# FPGA_Power_Ports.net
KiCad netlist of a schematic drawn in Altium Designer
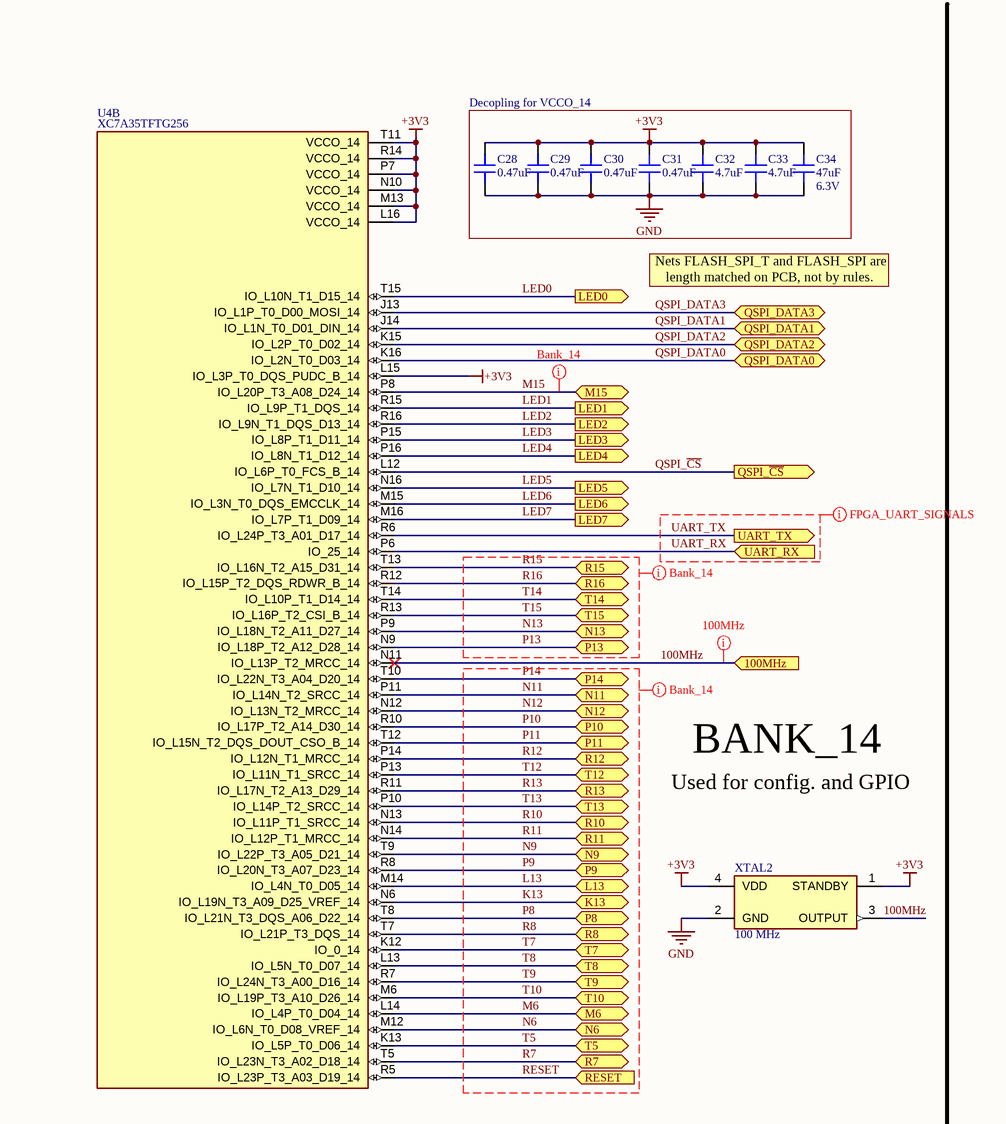
[diagram p0: FPGA_Power&Ports.SchDoc, top left]
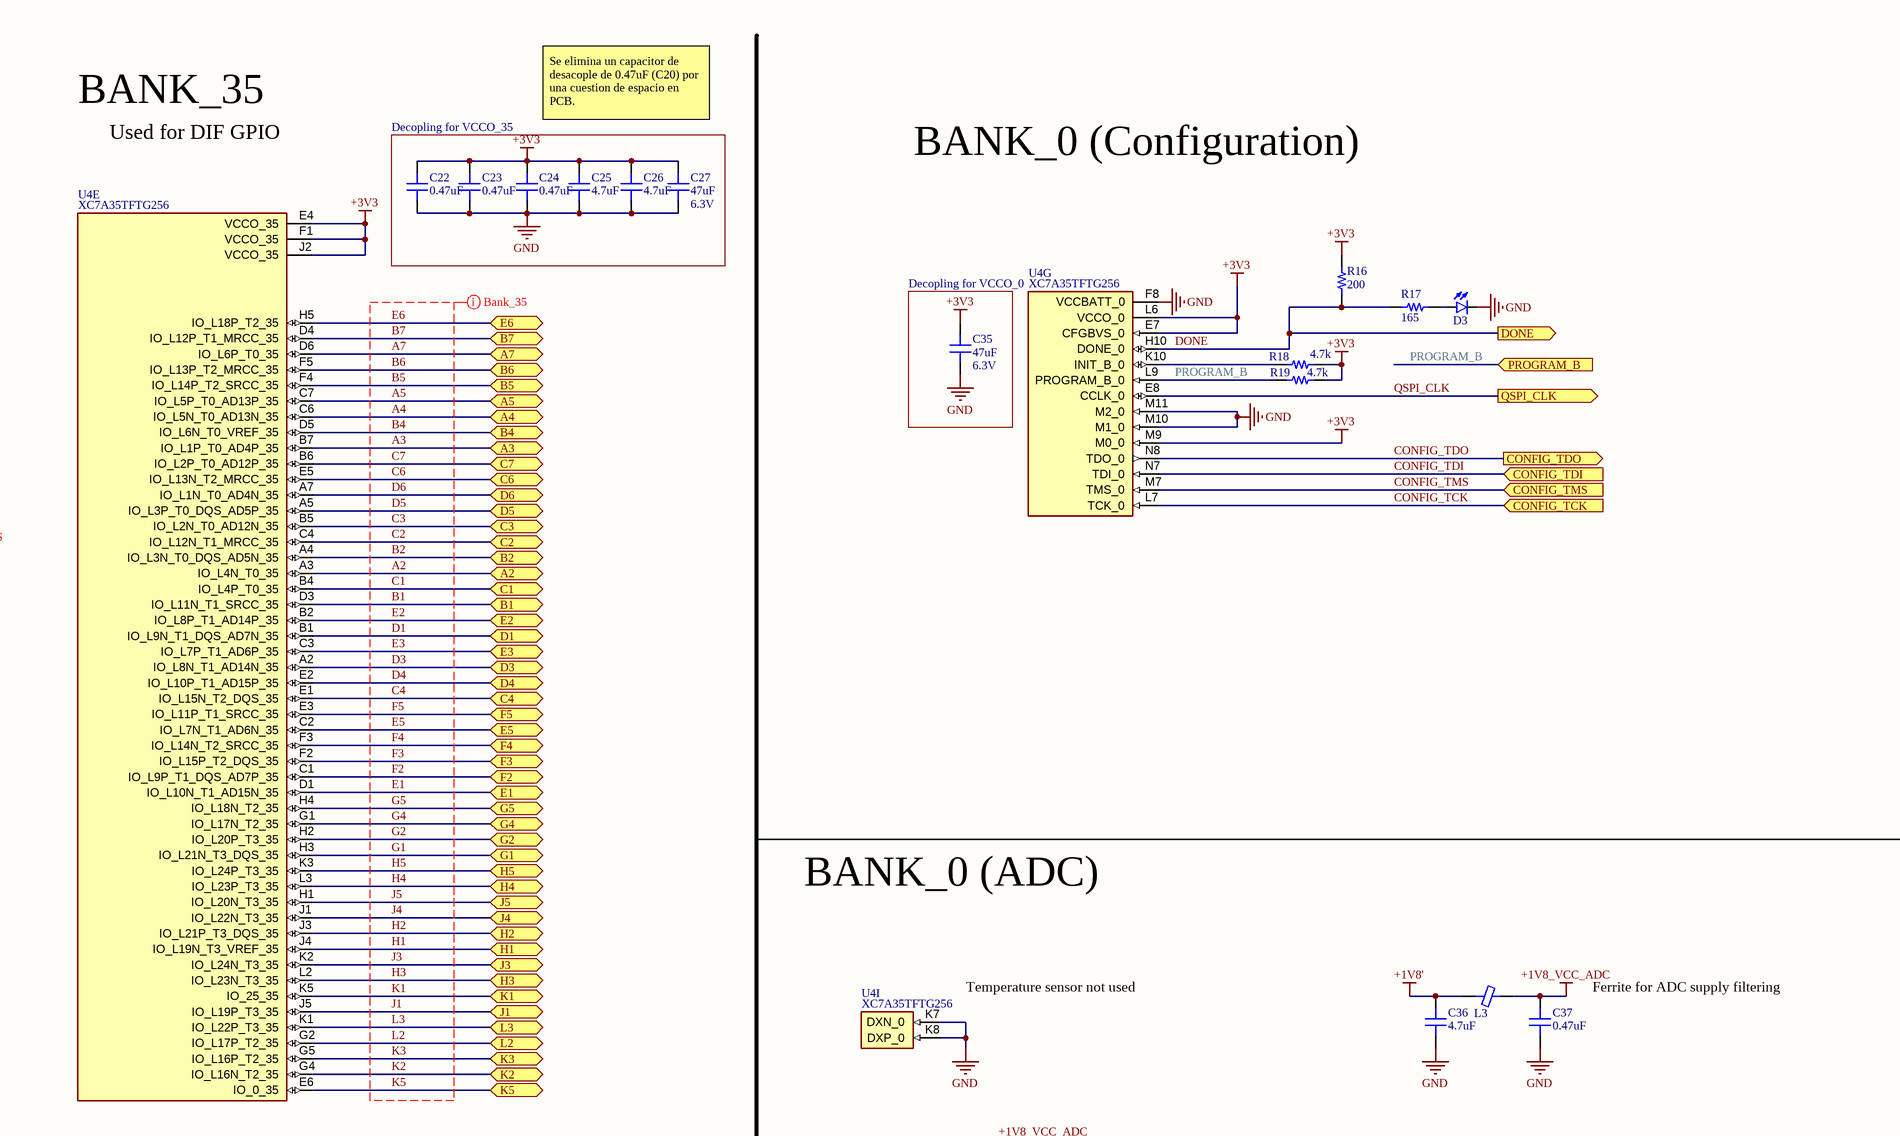
[diagram p1: FPGA_Power&Ports.SchDoc, top right]
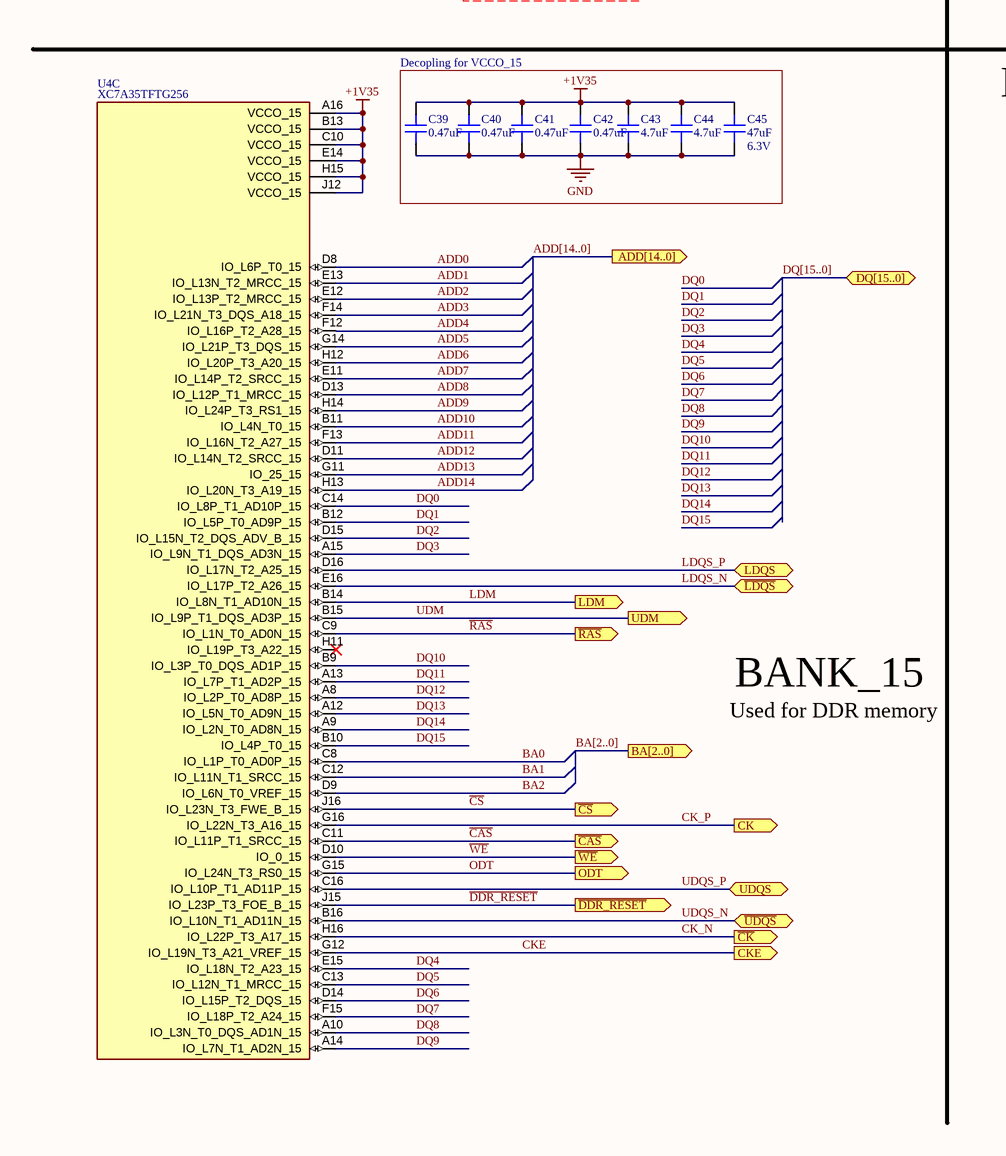
[diagram p2: FPGA_Power&Ports.SchDoc, bottom left]
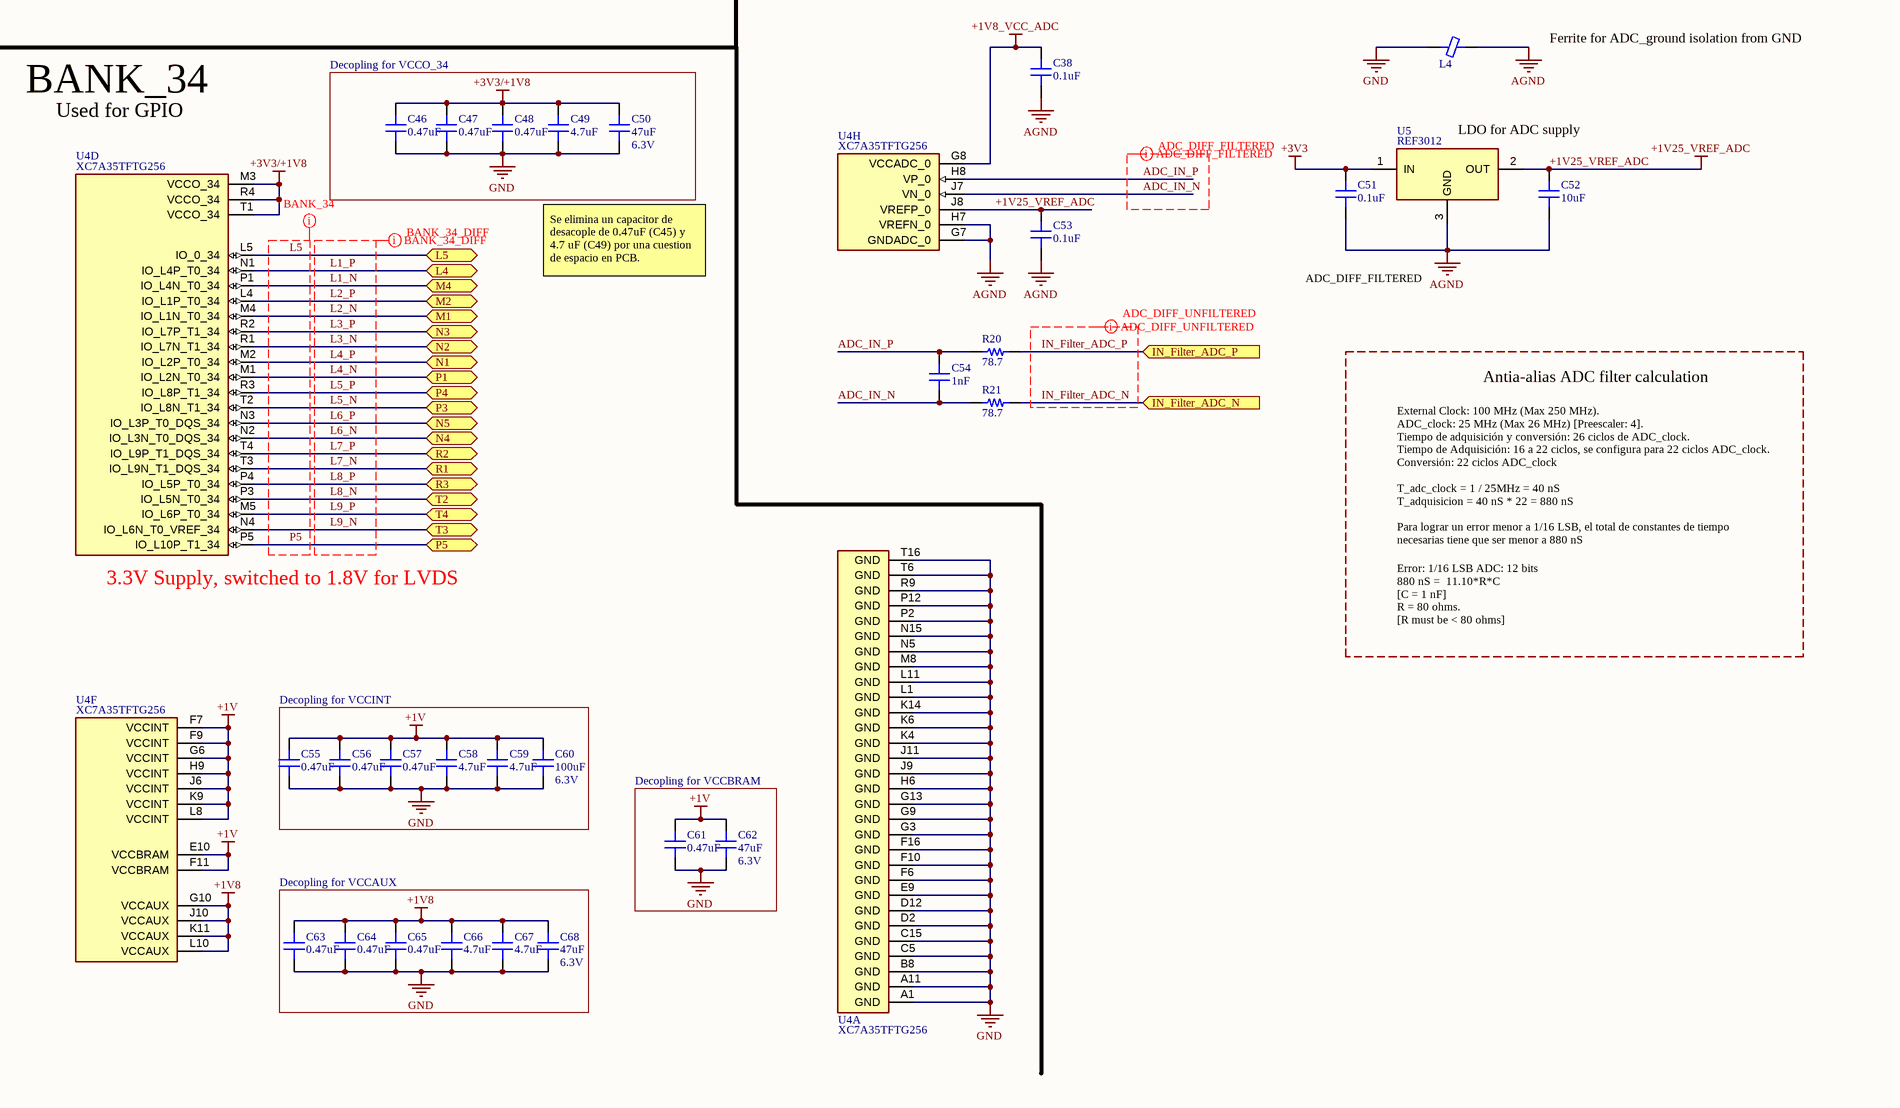
[diagram p3: FPGA_Power&Ports.SchDoc, bottom right]

(export (version "E")
  (design (tool "Eeschema 10.0.6"))
  (components
    (comp (ref "C22")
      (value "0.47uF")
      (footprint "CAP0402")
      (description "CAP CER 0.47uF 10V X7R 0402 10%")
      (fields (field (name "PARTNUMBER") "C0603C474K4RAC") (field (name "TOLERANCE") "10%"))
      (libsource (lib "Pasivos") (part "C0402C474K8RAC"))
    )
    (comp (ref "C23")
      (value "0.47uF")
      (footprint "CAP0402")
      (description "CAP CER 0.47uF 10V X7R 0402 10%")
      (fields (field (name "PARTNUMBER") "C0603C474K4RAC") (field (name "TOLERANCE") "10%"))
      (libsource (lib "Pasivos") (part "C0402C474K8RAC"))
    )
    (comp (ref "C24")
      (value "0.47uF")
      (footprint "CAP0402")
      (description "CAP CER 0.47uF 10V X7R 0402 10%")
      (fields (field (name "PARTNUMBER") "C0603C474K4RAC") (field (name "TOLERANCE") "10%"))
      (libsource (lib "Pasivos") (part "C0402C474K8RAC"))
    )
    (comp (ref "C25")
      (value "4.7uF")
      (footprint "CAP0402")
      (description "CAP CER 4.7uF 6.3V X5R 0402 10%")
      (fields (field (name "PARTNUMBER") "C0402C475M9PAC") (field (name "TOLERANCE") "10%"))
      (libsource (lib "Pasivos") (part "C0402C475M9PAC"))
    )
    (comp (ref "C26")
      (value "4.7uF")
      (footprint "CAP0402")
      (description "CAP CER 4.7uF 6.3V X5R 0402 10%")
      (fields (field (name "PARTNUMBER") "C0402C475M9PAC") (field (name "TOLERANCE") "10%"))
      (libsource (lib "Pasivos") (part "C0402C475M9PAC"))
    )
    (comp (ref "C27")
      (value "47uF")
      (footprint "CAP0805")
      (description "CAP CER 47uF 6.3V X5R 0805 20%")
      (fields
        (field (name "VOLTAGE") "6.3V")
        (field (name "MANUFACTURER") "Samsung")
        (field (name "TOLERANCE") "20%")
      )
      (libsource (lib "Pasivos") (part "CL21A476MQYNNNE"))
    )
    (comp (ref "C28")
      (value "0.47uF")
      (footprint "CAP0402")
      (description "CAP CER 0.47uF 10V X7R 0402 10%")
      (fields (field (name "PARTNUMBER") "C0603C474K4RAC") (field (name "TOLERANCE") "10%"))
      (libsource (lib "Pasivos") (part "C0402C474K8RAC"))
    )
    (comp (ref "C29")
      (value "0.47uF")
      (footprint "CAP0402")
      (description "CAP CER 0.47uF 10V X7R 0402 10%")
      (fields (field (name "PARTNUMBER") "C0603C474K4RAC") (field (name "TOLERANCE") "10%"))
      (libsource (lib "Pasivos") (part "C0402C474K8RAC"))
    )
    (comp (ref "C30")
      (value "0.47uF")
      (footprint "CAP0402")
      (description "CAP CER 0.47uF 10V X7R 0402 10%")
      (fields (field (name "PARTNUMBER") "C0603C474K4RAC") (field (name "TOLERANCE") "10%"))
      (libsource (lib "Pasivos") (part "C0402C474K8RAC"))
    )
    (comp (ref "C31")
      (value "0.47uF")
      (footprint "CAP0402")
      (description "CAP CER 0.47uF 10V X7R 0402 10%")
      (fields (field (name "PARTNUMBER") "C0603C474K4RAC") (field (name "TOLERANCE") "10%"))
      (libsource (lib "Pasivos") (part "C0402C474K8RAC"))
    )
    (comp (ref "C32")
      (value "4.7uF")
      (footprint "CAP0402")
      (description "CAP CER 4.7uF 6.3V X5R 0402 10%")
      (fields (field (name "PARTNUMBER") "C0402C475M9PAC") (field (name "TOLERANCE") "10%"))
      (libsource (lib "Pasivos") (part "C0402C475M9PAC"))
    )
    (comp (ref "C33")
      (value "4.7uF")
      (footprint "CAP0402")
      (description "CAP CER 4.7uF 6.3V X5R 0402 10%")
      (fields (field (name "PARTNUMBER") "C0402C475M9PAC") (field (name "TOLERANCE") "10%"))
      (libsource (lib "Pasivos") (part "C0402C475M9PAC"))
    )
    (comp (ref "C34")
      (value "47uF")
      (footprint "CAP0805")
      (description "CAP CER 47uF 6.3V X5R 0805 20%")
      (fields
        (field (name "VOLTAGE") "6.3V")
        (field (name "MANUFACTURER") "Samsung")
        (field (name "TOLERANCE") "20%")
      )
      (libsource (lib "Pasivos") (part "CL21A476MQYNNNE"))
    )
    (comp (ref "C35")
      (value "47uF")
      (footprint "CAP0805")
      (description "CAP CER 47uF 6.3V X5R 0805 20%")
      (fields
        (field (name "MANUFACTURER") "Samsung")
        (field (name "VOLTAGE") "6.3V")
        (field (name "TOLERANCE") "20%")
      )
      (libsource (lib "Pasivos") (part "CL21A476MQYNNNE"))
    )
    (comp (ref "C36")
      (value "4.7uF")
      (footprint "CAP0402")
      (description "CAP CER 4.7uF 6.3V X5R 0402 10%")
      (fields (field (name "PARTNUMBER") "C0402C475M9PAC") (field (name "TOLERANCE") "10%"))
      (libsource (lib "Pasivos") (part "C0402C475M9PAC"))
    )
    (comp (ref "C37")
      (value "0.47uF")
      (footprint "CAP0402")
      (description "CAP CER 0.47uF 10V X7R 0402 10%")
      (fields (field (name "PARTNUMBER") "C0603C474K4RAC") (field (name "TOLERANCE") "10%"))
      (libsource (lib "Pasivos") (part "C0402C474K8RAC"))
    )
    (comp (ref "C38")
      (value "0.1uF")
      (footprint "CAP0402")
      (description "CAP CER 0.1uF 16V X7R 0402 10%")
      (fields (field (name "TOLERANCE") "10%") (field (name "VOLTAGE") "16V"))
      (libsource (lib "Pasivos") (part "C0402C104K4RAC"))
    )
    (comp (ref "C39")
      (value "0.47uF")
      (footprint "CAP0402")
      (description "CAP CER 0.47uF 10V X7R 0402 10%")
      (fields (field (name "PARTNUMBER") "C0603C474K4RAC") (field (name "TOLERANCE") "10%"))
      (libsource (lib "Pasivos") (part "C0402C474K8RAC"))
    )
    (comp (ref "C40")
      (value "0.47uF")
      (footprint "CAP0402")
      (description "CAP CER 0.47uF 10V X7R 0402 10%")
      (fields (field (name "PARTNUMBER") "C0603C474K4RAC") (field (name "TOLERANCE") "10%"))
      (libsource (lib "Pasivos") (part "C0402C474K8RAC"))
    )
    (comp (ref "C41")
      (value "0.47uF")
      (footprint "CAP0402")
      (description "CAP CER 0.47uF 10V X7R 0402 10%")
      (fields (field (name "PARTNUMBER") "C0603C474K4RAC") (field (name "TOLERANCE") "10%"))
      (libsource (lib "Pasivos") (part "C0402C474K8RAC"))
    )
    (comp (ref "C42")
      (value "0.47uF")
      (footprint "CAP0402")
      (description "CAP CER 0.47uF 10V X7R 0402 10%")
      (fields (field (name "PARTNUMBER") "C0603C474K4RAC") (field (name "TOLERANCE") "10%"))
      (libsource (lib "Pasivos") (part "C0402C474K8RAC"))
    )
    (comp (ref "C43")
      (value "4.7uF")
      (footprint "CAP0402")
      (description "CAP CER 4.7uF 6.3V X5R 0402 10%")
      (fields (field (name "PARTNUMBER") "C0402C475M9PAC") (field (name "TOLERANCE") "10%"))
      (libsource (lib "Pasivos") (part "C0402C475M9PAC"))
    )
    (comp (ref "C44")
      (value "4.7uF")
      (footprint "CAP0402")
      (description "CAP CER 4.7uF 6.3V X5R 0402 10%")
      (fields (field (name "PARTNUMBER") "C0402C475M9PAC") (field (name "TOLERANCE") "10%"))
      (libsource (lib "Pasivos") (part "C0402C475M9PAC"))
    )
    (comp (ref "C45")
      (value "47uF")
      (footprint "CAP0805")
      (description "CAP CER 47uF 6.3V X5R 0805 20%")
      (fields
        (field (name "VOLTAGE") "6.3V")
        (field (name "MANUFACTURER") "Samsung")
        (field (name "TOLERANCE") "20%")
      )
      (libsource (lib "Pasivos") (part "CL21A476MQYNNNE"))
    )
    (comp (ref "C46")
      (value "0.47uF")
      (footprint "CAP0402")
      (description "CAP CER 0.47uF 10V X7R 0402 10%")
      (fields (field (name "PARTNUMBER") "C0603C474K4RAC") (field (name "TOLERANCE") "10%"))
      (libsource (lib "Pasivos") (part "C0402C474K8RAC"))
    )
    (comp (ref "C47")
      (value "0.47uF")
      (footprint "CAP0402")
      (description "CAP CER 0.47uF 10V X7R 0402 10%")
      (fields (field (name "PARTNUMBER") "C0603C474K4RAC") (field (name "TOLERANCE") "10%"))
      (libsource (lib "Pasivos") (part "C0402C474K8RAC"))
    )
    (comp (ref "C48")
      (value "0.47uF")
      (footprint "CAP0402")
      (description "CAP CER 0.47uF 10V X7R 0402 10%")
      (fields (field (name "PARTNUMBER") "C0603C474K4RAC") (field (name "TOLERANCE") "10%"))
      (libsource (lib "Pasivos") (part "C0402C474K8RAC"))
    )
    (comp (ref "C49")
      (value "4.7uF")
      (footprint "CAP0402")
      (description "CAP CER 4.7uF 6.3V X5R 0402 10%")
      (fields (field (name "PARTNUMBER") "C0402C475M9PAC") (field (name "TOLERANCE") "10%"))
      (libsource (lib "Pasivos") (part "C0402C475M9PAC"))
    )
    (comp (ref "C50")
      (value "47uF")
      (footprint "CAP0805")
      (description "CAP CER 47uF 6.3V X5R 0805 20%")
      (fields
        (field (name "VOLTAGE") "6.3V")
        (field (name "MANUFACTURER") "Samsung")
        (field (name "TOLERANCE") "20%")
      )
      (libsource (lib "Pasivos") (part "CL21A476MQYNNNE"))
    )
    (comp (ref "C51")
      (value "0.1uF")
      (footprint "CAP0402")
      (description "CAP CER 0.1uF 16V X7R 0402 10%")
      (fields (field (name "TOLERANCE") "10%") (field (name "VOLTAGE") "16V"))
      (libsource (lib "Pasivos") (part "C0402C104K4RAC"))
    )
    (comp (ref "C52")
      (value "10uF")
      (footprint "CAP0402")
      (description "CAP CER 10uF 6.3V X5R 0402 10%")
      (fields (field (name "TOLERANCE") "10%") (field (name "MANUFACTURER") "Kemet"))
      (libsource (lib "Pasivos") (part "C0402C106M9PAC"))
    )
    (comp (ref "C53")
      (value "0.1uF")
      (footprint "CAP0402")
      (description "CAP CER 0.1uF 16V X7R 0402 10%")
      (fields (field (name "TOLERANCE") "10%") (field (name "VOLTAGE") "16V"))
      (libsource (lib "Pasivos") (part "C0402C104K4RAC"))
    )
    (comp (ref "C54")
      (value "1nF")
      (footprint "CAP0402")
      (description "CAP CER 1nF 16V X7R 0402 10%")
      (fields (field (name "TOLERANCE") "10%") (field (name "PARTNUMBER") "C0402C102K4RAC"))
      (libsource (lib "Pasivos") (part "C0402C102K4RAC"))
    )
    (comp (ref "C55")
      (value "0.47uF")
      (footprint "CAP0402")
      (description "CAP CER 0.47uF 10V X7R 0402 10%")
      (fields (field (name "PARTNUMBER") "C0603C474K4RAC") (field (name "TOLERANCE") "10%"))
      (libsource (lib "Pasivos") (part "C0402C474K8RAC"))
    )
    (comp (ref "C56")
      (value "0.47uF")
      (footprint "CAP0402")
      (description "CAP CER 0.47uF 10V X7R 0402 10%")
      (fields (field (name "PARTNUMBER") "C0603C474K4RAC") (field (name "TOLERANCE") "10%"))
      (libsource (lib "Pasivos") (part "C0402C474K8RAC"))
    )
    (comp (ref "C57")
      (value "0.47uF")
      (footprint "CAP0402")
      (description "CAP CER 0.47uF 10V X7R 0402 10%")
      (fields (field (name "PARTNUMBER") "C0603C474K4RAC") (field (name "TOLERANCE") "10%"))
      (libsource (lib "Pasivos") (part "C0402C474K8RAC"))
    )
    (comp (ref "C58")
      (value "4.7uF")
      (footprint "CAP0402")
      (description "CAP CER 4.7uF 6.3V X5R 0402 10%")
      (fields (field (name "PARTNUMBER") "C0402C475M9PAC") (field (name "TOLERANCE") "10%"))
      (libsource (lib "Pasivos") (part "C0402C475M9PAC"))
    )
    (comp (ref "C59")
      (value "4.7uF")
      (footprint "CAP0402")
      (description "CAP CER 4.7uF 6.3V X5R 0402 10%")
      (fields (field (name "PARTNUMBER") "C0402C475M9PAC") (field (name "TOLERANCE") "10%"))
      (libsource (lib "Pasivos") (part "C0402C475M9PAC"))
    )
    (comp (ref "C60")
      (value "100uF")
      (footprint "CAP1206")
      (description "CAP CER 100uF 6.3V X5R 1206 20%")
      (fields
        (field (name "PARTNUMBER") "C1206C107M9PAC")
        (field (name "TOLERANCE") "20%")
        (field (name "VOLTAGE") "6.3V")
      )
      (libsource (lib "Pasivos") (part "C1206C107M9PAC"))
    )
    (comp (ref "C61")
      (value "0.47uF")
      (footprint "CAP0402")
      (description "CAP CER 0.47uF 10V X7R 0402 10%")
      (fields (field (name "PARTNUMBER") "C0603C474K4RAC") (field (name "TOLERANCE") "10%"))
      (libsource (lib "Pasivos") (part "C0402C474K8RAC"))
    )
    (comp (ref "C62")
      (value "47uF")
      (footprint "CAP0805")
      (description "CAP CER 47uF 6.3V X5R 0805 20%")
      (fields
        (field (name "VOLTAGE") "6.3V")
        (field (name "MANUFACTURER") "Samsung")
        (field (name "TOLERANCE") "20%")
      )
      (libsource (lib "Pasivos") (part "CL21A476MQYNNNE"))
    )
    (comp (ref "C63")
      (value "0.47uF")
      (footprint "CAP0402")
      (description "CAP CER 0.47uF 10V X7R 0402 10%")
      (fields (field (name "PARTNUMBER") "C0603C474K4RAC") (field (name "TOLERANCE") "10%"))
      (libsource (lib "Pasivos") (part "C0402C474K8RAC"))
    )
    (comp (ref "C64")
      (value "0.47uF")
      (footprint "CAP0402")
      (description "CAP CER 0.47uF 10V X7R 0402 10%")
      (fields (field (name "PARTNUMBER") "C0603C474K4RAC") (field (name "TOLERANCE") "10%"))
      (libsource (lib "Pasivos") (part "C0402C474K8RAC"))
    )
    (comp (ref "C65")
      (value "0.47uF")
      (footprint "CAP0402")
      (description "CAP CER 0.47uF 10V X7R 0402 10%")
      (fields (field (name "PARTNUMBER") "C0603C474K4RAC") (field (name "TOLERANCE") "10%"))
      (libsource (lib "Pasivos") (part "C0402C474K8RAC"))
    )
    (comp (ref "C66")
      (value "4.7uF")
      (footprint "CAP0402")
      (description "CAP CER 4.7uF 6.3V X5R 0402 10%")
      (fields (field (name "PARTNUMBER") "C0402C475M9PAC") (field (name "TOLERANCE") "10%"))
      (libsource (lib "Pasivos") (part "C0402C475M9PAC"))
    )
    (comp (ref "C67")
      (value "4.7uF")
      (footprint "CAP0402")
      (description "CAP CER 4.7uF 6.3V X5R 0402 10%")
      (fields (field (name "PARTNUMBER") "C0402C475M9PAC") (field (name "TOLERANCE") "10%"))
      (libsource (lib "Pasivos") (part "C0402C475M9PAC"))
    )
    (comp (ref "C68")
      (value "47uF")
      (footprint "CAP0805")
      (description "CAP CER 47uF 6.3V X5R 0805 20%")
      (fields
        (field (name "VOLTAGE") "6.3V")
        (field (name "MANUFACTURER") "Samsung")
        (field (name "TOLERANCE") "20%")
      )
      (libsource (lib "Pasivos") (part "CL21A476MQYNNNE"))
    )
    (comp (ref "D3")
      (value "597-3305-607F")
      (footprint "0603_LED")
      (description "LED blue diffused 0603 SMD")
      (libsource (lib "Integrated_Circuits") (part "LED_BLUE_0603"))
    )
    (comp (ref "L3")
      (value "HZ0603C651R-10")
      (footprint "Fer0603")
      (description "FERRITE BEAD 650 OHM 0603 1LN 0603")
      (libsource (lib "Pasivos") (part "HZ0603C651R-10"))
    )
    (comp (ref "L4")
      (value "HZ0603C651R-10")
      (footprint "Fer0603")
      (description "FERRITE BEAD 650 OHM 0603 1LN 0603")
      (libsource (lib "Pasivos") (part "HZ0603C651R-10"))
    )
    (comp (ref "R16")
      (value "200")
      (footprint "RES0402")
      (description "RES SMD 200 OHM 1% 0.063W 0402")
      (fields (field (name "POWER") "0.063W") (field (name "MANUFACTURER") "Vishay"))
      (libsource (lib "Pasivos") (part "CRCW0402200RFK"))
    )
    (comp (ref "R17")
      (value "165")
      (footprint "RES0402")
      (description "RES SMD 165 OHM 1% 0.063W 0402")
      (fields (field (name "MANUFACTURER") "Vishay") (field (name "TOLERANCE") "1%"))
      (libsource (lib "Pasivos") (part "CRCW0402165RFK"))
    )
    (comp (ref "R18")
      (value "4.7k")
      (footprint "RES0402")
      (description "RES SMD 4.7K OHM 1% 0.063W 0402")
      (fields (field (name "POWER") "0.063 W") (field (name "MANUFACTURER") "Vishay"))
      (libsource (lib "Pasivos") (part "CRCW04024K70FK"))
    )
    (comp (ref "R19")
      (value "4.7k")
      (footprint "RES0402")
      (description "RES SMD 4.7K OHM 1% 0.063W 0402")
      (fields (field (name "POWER") "0.063 W") (field (name "MANUFACTURER") "Vishay"))
      (libsource (lib "Pasivos") (part "CRCW04024K70FK"))
    )
    (comp (ref "R20")
      (value "78.7")
      (footprint "RES0402")
      (description "RES SMD 78.7 OHM 1% 0.063W 0402")
      (fields (field (name "MANUFACTURER") "Vishay") (field (name "TOLERANCE") "1%"))
      (libsource (lib "Pasivos") (part "CRCW040278R7FK"))
    )
    (comp (ref "R21")
      (value "78.7")
      (footprint "RES0402")
      (description "RES SMD 78.7 OHM 1% 0.063W 0402")
      (fields (field (name "MANUFACTURER") "Vishay") (field (name "TOLERANCE") "1%"))
      (libsource (lib "Pasivos") (part "CRCW040278R7FK"))
    )
    (comp (ref "U4")
      (value "XC7A35TFTG256")
      (footprint "BGA-256")
      (description "FPGA")
      (libsource (lib "Integrated_Circuits") (part "XC7A35TFTG256"))
    )
    (comp (ref "U5")
      (value "REF3012")
      (footprint "SOT23-3")
      (description "Voltage Reference 1,5V")
      (libsource (lib "Integrated_Circuits") (part "REF3012"))
    )
    (comp (ref "XTAL2")
      (value "ASFLMB-100.000MHZ-LC-T")
      (footprint "XTAL_ASFLMB")
      (description "Crystal 100 MHz")
      (fields (field (name "MANUFACTURER") "Abracom") (field (name "FREQUENCY") "100 MHz"))
      (libsource (lib "Integrated_Circuits") (part "XTAL_100MHz"))
    )
  )
  (nets
    (net (code "1") (name "+1V") (class "Default")
      (node (ref "C55") (pin "2") (pinfunction "2_2") (pintype "passive"))
      (node (ref "C56") (pin "2") (pinfunction "2_2") (pintype "passive"))
      (node (ref "C57") (pin "2") (pinfunction "2_2") (pintype "passive"))
      (node (ref "C58") (pin "2") (pinfunction "2_2") (pintype "passive"))
      (node (ref "C59") (pin "2") (pinfunction "2_2") (pintype "passive"))
      (node (ref "C60") (pin "2") (pinfunction "2_2") (pintype "passive"))
      (node (ref "C61") (pin "2") (pinfunction "2_2") (pintype "passive"))
      (node (ref "C62") (pin "2") (pinfunction "2_2") (pintype "passive"))
      (node (ref "U4") (pin "E10") (pinfunction "VCCBRAM_E10") (pintype "power_in"))
      (node (ref "U4") (pin "F11") (pinfunction "VCCBRAM_F11") (pintype "power_in"))
      (node (ref "U4") (pin "F7") (pinfunction "VCCINT_F7") (pintype "power_in"))
      (node (ref "U4") (pin "F9") (pinfunction "VCCINT_F9") (pintype "power_in"))
      (node (ref "U4") (pin "G6") (pinfunction "VCCINT_G6") (pintype "power_in"))
      (node (ref "U4") (pin "H9") (pinfunction "VCCINT_H9") (pintype "power_in"))
      (node (ref "U4") (pin "J6") (pinfunction "VCCINT_J6") (pintype "power_in"))
      (node (ref "U4") (pin "K9") (pinfunction "VCCINT_K9") (pintype "power_in"))
      (node (ref "U4") (pin "L8") (pinfunction "VCCINT_L8") (pintype "power_in"))
    )
    (net (code "2") (name "+1V8") (class "Default")
      (node (ref "C63") (pin "2") (pinfunction "2_2") (pintype "passive"))
      (node (ref "C64") (pin "2") (pinfunction "2_2") (pintype "passive"))
      (node (ref "C65") (pin "2") (pinfunction "2_2") (pintype "passive"))
      (node (ref "C66") (pin "2") (pinfunction "2_2") (pintype "passive"))
      (node (ref "C67") (pin "2") (pinfunction "2_2") (pintype "passive"))
      (node (ref "C68") (pin "2") (pinfunction "2_2") (pintype "passive"))
      (node (ref "U4") (pin "G10") (pinfunction "VCCAUX_G10") (pintype "power_in"))
      (node (ref "U4") (pin "J10") (pinfunction "VCCAUX_J10") (pintype "power_in"))
      (node (ref "U4") (pin "K11") (pinfunction "VCCAUX_K11") (pintype "power_in"))
      (node (ref "U4") (pin "L10") (pinfunction "VCCAUX_L10") (pintype "power_in"))
    )
    (net (code "3") (name "+1V8'") (class "Default")
      (node (ref "C36") (pin "2") (pinfunction "2_2") (pintype "passive"))
      (node (ref "L3") (pin "1") (pinfunction "1_1") (pintype "passive"))
    )
    (net (code "4") (name "+1V8_VCC_ADC") (class "Default")
      (node (ref "C37") (pin "2") (pinfunction "2_2") (pintype "passive"))
      (node (ref "C38") (pin "2") (pinfunction "2_2") (pintype "passive"))
      (node (ref "L3") (pin "2") (pinfunction "2_2") (pintype "passive"))
      (node (ref "U4") (pin "G8") (pinfunction "VCCADC_0_G8") (pintype "power_in"))
    )
    (net (code "5") (name "+1V25_VREF_ADC") (class "Default")
      (node (ref "C52") (pin "2") (pinfunction "2_2") (pintype "passive"))
      (node (ref "C53") (pin "2") (pinfunction "2_2") (pintype "passive"))
      (node (ref "U4") (pin "J8") (pinfunction "VREFP_0_J8") (pintype "power_in"))
      (node (ref "U5") (pin "2") (pinfunction "OUT_2") (pintype "power_in"))
    )
    (net (code "6") (name "+1V35") (class "Default")
      (node (ref "C39") (pin "2") (pinfunction "2_2") (pintype "passive"))
      (node (ref "C40") (pin "2") (pinfunction "2_2") (pintype "passive"))
      (node (ref "C41") (pin "2") (pinfunction "2_2") (pintype "passive"))
      (node (ref "C42") (pin "2") (pinfunction "2_2") (pintype "passive"))
      (node (ref "C43") (pin "2") (pinfunction "2_2") (pintype "passive"))
      (node (ref "C44") (pin "2") (pinfunction "2_2") (pintype "passive"))
      (node (ref "C45") (pin "2") (pinfunction "2_2") (pintype "passive"))
      (node (ref "U4") (pin "A16") (pinfunction "VCCO_15_A16") (pintype "power_in"))
      (node (ref "U4") (pin "B13") (pinfunction "VCCO_15_B13") (pintype "power_in"))
      (node (ref "U4") (pin "C10") (pinfunction "VCCO_15_C10") (pintype "power_in"))
      (node (ref "U4") (pin "E14") (pinfunction "VCCO_15_E14") (pintype "power_in"))
      (node (ref "U4") (pin "H15") (pinfunction "VCCO_15_H15") (pintype "power_in"))
      (node (ref "U4") (pin "J12") (pinfunction "VCCO_15_J12") (pintype "power_in"))
    )
    (net (code "7") (name "+3V3") (class "Default")
      (node (ref "C22") (pin "2") (pinfunction "2_2") (pintype "passive"))
      (node (ref "C23") (pin "2") (pinfunction "2_2") (pintype "passive"))
      (node (ref "C24") (pin "2") (pinfunction "2_2") (pintype "passive"))
      (node (ref "C25") (pin "2") (pinfunction "2_2") (pintype "passive"))
      (node (ref "C26") (pin "2") (pinfunction "2_2") (pintype "passive"))
      (node (ref "C27") (pin "2") (pinfunction "2_2") (pintype "passive"))
      (node (ref "C28") (pin "2") (pinfunction "2_2") (pintype "passive"))
      (node (ref "C29") (pin "2") (pinfunction "2_2") (pintype "passive"))
      (node (ref "C30") (pin "2") (pinfunction "2_2") (pintype "passive"))
      (node (ref "C31") (pin "2") (pinfunction "2_2") (pintype "passive"))
      (node (ref "C32") (pin "2") (pinfunction "2_2") (pintype "passive"))
      (node (ref "C33") (pin "2") (pinfunction "2_2") (pintype "passive"))
      (node (ref "C34") (pin "2") (pinfunction "2_2") (pintype "passive"))
      (node (ref "C35") (pin "2") (pinfunction "2_2") (pintype "passive"))
      (node (ref "C51") (pin "2") (pinfunction "2_2") (pintype "passive"))
      (node (ref "R16") (pin "2") (pinfunction "2_2") (pintype "passive"))
      (node (ref "R18") (pin "2") (pinfunction "2_2") (pintype "passive"))
      (node (ref "R19") (pin "2") (pinfunction "2_2") (pintype "passive"))
      (node (ref "U4") (pin "E4") (pinfunction "VCCO_35_E4") (pintype "power_in"))
      (node (ref "U4") (pin "E7") (pinfunction "CFGBVS_0_E7") (pintype "input"))
      (node (ref "U4") (pin "F1") (pinfunction "VCCO_35_F1") (pintype "power_in"))
      (node (ref "U4") (pin "J2") (pinfunction "VCCO_35_J2") (pintype "power_in"))
      (node (ref "U4") (pin "L15") (pinfunction "IO_L3P_T0_DQS_PUDC_B_14_L15") (pintype "bidirectional"))
      (node (ref "U4") (pin "L16") (pinfunction "VCCO_14_L16") (pintype "power_in"))
      (node (ref "U4") (pin "L6") (pinfunction "VCCO_0_L6") (pintype "power_in"))
      (node (ref "U4") (pin "M13") (pinfunction "VCCO_14_M13") (pintype "power_in"))
      (node (ref "U4") (pin "M9") (pinfunction "M0_0_M9") (pintype "input"))
      (node (ref "U4") (pin "N10") (pinfunction "VCCO_14_N10") (pintype "power_in"))
      (node (ref "U4") (pin "P7") (pinfunction "VCCO_14_P7") (pintype "power_in"))
      (node (ref "U4") (pin "R14") (pinfunction "VCCO_14_R14") (pintype "power_in"))
      (node (ref "U4") (pin "T11") (pinfunction "VCCO_14_T11") (pintype "power_in"))
      (node (ref "U5") (pin "1") (pinfunction "IN_1") (pintype "power_in"))
      (node (ref "XTAL2") (pin "1") (pinfunction "STANDBY_1") (pintype "passive"))
      (node (ref "XTAL2") (pin "4") (pinfunction "VDD_4") (pintype "power_in"))
    )
    (net (code "8") (name "+3V3{slash}+1V8") (class "Default")
      (node (ref "C46") (pin "2") (pinfunction "2_2") (pintype "passive"))
      (node (ref "C47") (pin "2") (pinfunction "2_2") (pintype "passive"))
      (node (ref "C48") (pin "2") (pinfunction "2_2") (pintype "passive"))
      (node (ref "C49") (pin "2") (pinfunction "2_2") (pintype "passive"))
      (node (ref "C50") (pin "2") (pinfunction "2_2") (pintype "passive"))
      (node (ref "U4") (pin "M3") (pinfunction "VCCO_34_M3") (pintype "power_in"))
      (node (ref "U4") (pin "R4") (pinfunction "VCCO_34_R4") (pintype "power_in"))
      (node (ref "U4") (pin "T1") (pinfunction "VCCO_34_T1") (pintype "power_in"))
    )
    (net (code "9") (name "/100MHz") (class "Default")
      (node (ref "U4") (pin "N11") (pinfunction "IO_L13P_T2_MRCC_14_N11") (pintype "bidirectional"))
      (node (ref "XTAL2") (pin "3") (pinfunction "OUTPUT_3") (pintype "output"))
    )
    (net (code "10") (name "/A2") (class "Default")
      (node (ref "U4") (pin "A3") (pinfunction "IO_L4N_T0_35_A3") (pintype "bidirectional"))
    )
    (net (code "11") (name "/A3") (class "Default")
      (node (ref "U4") (pin "B7") (pinfunction "IO_L1P_T0_AD4P_35_B7") (pintype "bidirectional"))
    )
    (net (code "12") (name "/A4") (class "Default")
      (node (ref "U4") (pin "C6") (pinfunction "IO_L5N_T0_AD13N_35_C6") (pintype "bidirectional"))
    )
    (net (code "13") (name "/A5") (class "Default")
      (node (ref "U4") (pin "C7") (pinfunction "IO_L5P_T0_AD13P_35_C7") (pintype "bidirectional"))
    )
    (net (code "14") (name "/A7") (class "Default")
      (node (ref "U4") (pin "D6") (pinfunction "IO_L6P_T0_35_D6") (pintype "bidirectional"))
    )
    (net (code "15") (name "/ADC_IN_N") (class "Default")
      (node (ref "C54") (pin "1") (pinfunction "1_1") (pintype "passive"))
      (node (ref "R21") (pin "1") (pinfunction "1_1") (pintype "passive"))
      (node (ref "U4") (pin "J7") (pinfunction "VN_0_J7") (pintype "input"))
    )
    (net (code "16") (name "/ADC_IN_P") (class "Default")
      (node (ref "C54") (pin "2") (pinfunction "2_2") (pintype "passive"))
      (node (ref "R20") (pin "1") (pinfunction "1_1") (pintype "passive"))
      (node (ref "U4") (pin "H8") (pinfunction "VP_0_H8") (pintype "input"))
    )
    (net (code "17") (name "/ADD0") (class "Default")
      (node (ref "U4") (pin "D8") (pinfunction "IO_L6P_T0_15_D8") (pintype "bidirectional"))
    )
    (net (code "18") (name "/ADD1") (class "Default")
      (node (ref "U4") (pin "E13") (pinfunction "IO_L13N_T2_MRCC_15_E13") (pintype "bidirectional"))
    )
    (net (code "19") (name "/ADD2") (class "Default")
      (node (ref "U4") (pin "E12") (pinfunction "IO_L13P_T2_MRCC_15_E12") (pintype "bidirectional"))
    )
    (net (code "20") (name "/ADD3") (class "Default")
      (node (ref "U4") (pin "F14") (pinfunction "IO_L21N_T3_DQS_A18_15_F14") (pintype "bidirectional"))
    )
    (net (code "21") (name "/ADD4") (class "Default")
      (node (ref "U4") (pin "F12") (pinfunction "IO_L16P_T2_A28_15_F12") (pintype "bidirectional"))
    )
    (net (code "22") (name "/ADD5") (class "Default")
      (node (ref "U4") (pin "G14") (pinfunction "IO_L21P_T3_DQS_15_G14") (pintype "bidirectional"))
    )
    (net (code "23") (name "/ADD6") (class "Default")
      (node (ref "U4") (pin "H12") (pinfunction "IO_L20P_T3_A20_15_H12") (pintype "bidirectional"))
    )
    (net (code "24") (name "/ADD7") (class "Default")
      (node (ref "U4") (pin "E11") (pinfunction "IO_L14P_T2_SRCC_15_E11") (pintype "bidirectional"))
    )
    (net (code "25") (name "/ADD8") (class "Default")
      (node (ref "U4") (pin "D13") (pinfunction "IO_L12P_T1_MRCC_15_D13") (pintype "bidirectional"))
    )
    (net (code "26") (name "/ADD9") (class "Default")
      (node (ref "U4") (pin "H14") (pinfunction "IO_L24P_T3_RS1_15_H14") (pintype "bidirectional"))
    )
    (net (code "27") (name "/ADD10") (class "Default")
      (node (ref "U4") (pin "B11") (pinfunction "IO_L4N_T0_15_B11") (pintype "bidirectional"))
    )
    (net (code "28") (name "/ADD11") (class "Default")
      (node (ref "U4") (pin "F13") (pinfunction "IO_L16N_T2_A27_15_F13") (pintype "bidirectional"))
    )
    (net (code "29") (name "/ADD12") (class "Default")
      (node (ref "U4") (pin "D11") (pinfunction "IO_L14N_T2_SRCC_15_D11") (pintype "bidirectional"))
    )
    (net (code "30") (name "/ADD13") (class "Default")
      (node (ref "U4") (pin "G11") (pinfunction "IO_25_15_G11") (pintype "bidirectional"))
    )
    (net (code "31") (name "/ADD14") (class "Default")
      (node (ref "U4") (pin "H13") (pinfunction "IO_L20N_T3_A19_15_H13") (pintype "bidirectional"))
    )
    (net (code "33") (name "/B1") (class "Default")
      (node (ref "U4") (pin "D3") (pinfunction "IO_L11N_T1_SRCC_35_D3") (pintype "bidirectional"))
    )
    (net (code "34") (name "/B2") (class "Default")
      (node (ref "U4") (pin "A4") (pinfunction "IO_L3N_T0_DQS_AD5N_35_A4") (pintype "bidirectional"))
    )
    (net (code "35") (name "/B4") (class "Default")
      (node (ref "U4") (pin "D5") (pinfunction "IO_L6N_T0_VREF_35_D5") (pintype "bidirectional"))
    )
    (net (code "36") (name "/B5") (class "Default")
      (node (ref "U4") (pin "F4") (pinfunction "IO_L14P_T2_SRCC_35_F4") (pintype "bidirectional"))
    )
    (net (code "37") (name "/B6") (class "Default")
      (node (ref "U4") (pin "F5") (pinfunction "IO_L13P_T2_MRCC_35_F5") (pintype "bidirectional"))
    )
    (net (code "38") (name "/B7") (class "Default")
      (node (ref "U4") (pin "D4") (pinfunction "IO_L12P_T1_MRCC_35_D4") (pintype "bidirectional"))
    )
    (net (code "39") (name "/BA0") (class "Default")
      (node (ref "U4") (pin "C8") (pinfunction "IO_L1P_T0_AD0P_15_C8") (pintype "bidirectional"))
    )
    (net (code "40") (name "/BA1") (class "Default")
      (node (ref "U4") (pin "C12") (pinfunction "IO_L11N_T1_SRCC_15_C12") (pintype "bidirectional"))
    )
    (net (code "41") (name "/BA2") (class "Default")
      (node (ref "U4") (pin "D9") (pinfunction "IO_L6N_T0_VREF_15_D9") (pintype "bidirectional"))
    )
    (net (code "43") (name "/C1") (class "Default")
      (node (ref "U4") (pin "B4") (pinfunction "IO_L4P_T0_35_B4") (pintype "bidirectional"))
    )
    (net (code "44") (name "/C2") (class "Default")
      (node (ref "U4") (pin "C4") (pinfunction "IO_L12N_T1_MRCC_35_C4") (pintype "bidirectional"))
    )
    (net (code "45") (name "/C3") (class "Default")
      (node (ref "U4") (pin "B5") (pinfunction "IO_L2N_T0_AD12N_35_B5") (pintype "bidirectional"))
    )
    (net (code "46") (name "/C4") (class "Default")
      (node (ref "U4") (pin "E1") (pinfunction "IO_L15N_T2_DQS_35_E1") (pintype "bidirectional"))
    )
    (net (code "47") (name "/C6") (class "Default")
      (node (ref "U4") (pin "E5") (pinfunction "IO_L13N_T2_MRCC_35_E5") (pintype "bidirectional"))
    )
    (net (code "48") (name "/C7") (class "Default")
      (node (ref "U4") (pin "B6") (pinfunction "IO_L2P_T0_AD12P_35_B6") (pintype "bidirectional"))
    )
    (net (code "49") (name "/CKE") (class "Default")
      (node (ref "U4") (pin "G12") (pinfunction "IO_L19N_T3_A21_VREF_15_G12") (pintype "bidirectional"))
    )
    (net (code "50") (name "/CK_N") (class "Default")
      (node (ref "U4") (pin "H16") (pinfunction "IO_L22P_T3_A17_15_H16") (pintype "bidirectional"))
    )
    (net (code "51") (name "/CK_P") (class "Default")
      (node (ref "U4") (pin "G16") (pinfunction "IO_L22N_T3_A16_15_G16") (pintype "bidirectional"))
    )
    (net (code "52") (name "/CONFIG_TCK") (class "Default")
      (node (ref "U4") (pin "L7") (pinfunction "TCK_0_L7") (pintype "input"))
    )
    (net (code "53") (name "/CONFIG_TDI") (class "Default")
      (node (ref "U4") (pin "N7") (pinfunction "TDI_0_N7") (pintype "input"))
    )
    (net (code "54") (name "/CONFIG_TDO") (class "Default")
      (node (ref "U4") (pin "N8") (pinfunction "TDO_0_N8") (pintype "output"))
    )
    (net (code "55") (name "/CONFIG_TMS") (class "Default")
      (node (ref "U4") (pin "M7") (pinfunction "TMS_0_M7") (pintype "input"))
    )
    (net (code "56") (name "/D1") (class "Default")
      (node (ref "U4") (pin "B1") (pinfunction "IO_L9N_T1_DQS_AD7N_35_B1") (pintype "bidirectional"))
    )
    (net (code "57") (name "/D3") (class "Default")
      (node (ref "U4") (pin "A2") (pinfunction "IO_L8N_T1_AD14N_35_A2") (pintype "bidirectional"))
    )
    (net (code "58") (name "/D4") (class "Default")
      (node (ref "U4") (pin "E2") (pinfunction "IO_L10P_T1_AD15P_35_E2") (pintype "bidirectional"))
    )
    (net (code "59") (name "/D5") (class "Default")
      (node (ref "U4") (pin "A5") (pinfunction "IO_L3P_T0_DQS_AD5P_35_A5") (pintype "bidirectional"))
    )
    (net (code "60") (name "/D6") (class "Default")
      (node (ref "U4") (pin "A7") (pinfunction "IO_L1N_T0_AD4N_35_A7") (pintype "bidirectional"))
    )
    (net (code "61") (name "/DONE") (class "Default")
      (node (ref "R16") (pin "1") (pinfunction "1_1") (pintype "passive"))
      (node (ref "R17") (pin "1") (pinfunction "1_1") (pintype "passive"))
      (node (ref "U4") (pin "H10") (pinfunction "DONE_0_H10") (pintype "bidirectional"))
    )
    (net (code "62") (name "/DQ0") (class "Default")
      (node (ref "U4") (pin "C14") (pinfunction "IO_L8P_T1_AD10P_15_C14") (pintype "bidirectional"))
    )
    (net (code "63") (name "/DQ1") (class "Default")
      (node (ref "U4") (pin "B12") (pinfunction "IO_L5P_T0_AD9P_15_B12") (pintype "bidirectional"))
    )
    (net (code "64") (name "/DQ2") (class "Default")
      (node (ref "U4") (pin "D15") (pinfunction "IO_L15N_T2_DQS_ADV_B_15_D15") (pintype "bidirectional"))
    )
    (net (code "65") (name "/DQ3") (class "Default")
      (node (ref "U4") (pin "A15") (pinfunction "IO_L9N_T1_DQS_AD3N_15_A15") (pintype "bidirectional"))
    )
    (net (code "66") (name "/DQ4") (class "Default")
      (node (ref "U4") (pin "E15") (pinfunction "IO_L18N_T2_A23_15_E15") (pintype "bidirectional"))
    )
    (net (code "67") (name "/DQ5") (class "Default")
      (node (ref "U4") (pin "C13") (pinfunction "IO_L12N_T1_MRCC_15_C13") (pintype "bidirectional"))
    )
    (net (code "68") (name "/DQ6") (class "Default")
      (node (ref "U4") (pin "D14") (pinfunction "IO_L15P_T2_DQS_15_D14") (pintype "bidirectional"))
    )
    (net (code "69") (name "/DQ7") (class "Default")
      (node (ref "U4") (pin "F15") (pinfunction "IO_L18P_T2_A24_15_F15") (pintype "bidirectional"))
    )
    (net (code "70") (name "/DQ8") (class "Default")
      (node (ref "U4") (pin "A10") (pinfunction "IO_L3N_T0_DQS_AD1N_15_A10") (pintype "bidirectional"))
    )
    (net (code "71") (name "/DQ9") (class "Default")
      (node (ref "U4") (pin "A14") (pinfunction "IO_L7N_T1_AD2N_15_A14") (pintype "bidirectional"))
    )
    (net (code "72") (name "/DQ10") (class "Default")
      (node (ref "U4") (pin "B9") (pinfunction "IO_L3P_T0_DQS_AD1P_15_B9") (pintype "bidirectional"))
    )
    (net (code "73") (name "/DQ11") (class "Default")
      (node (ref "U4") (pin "A13") (pinfunction "IO_L7P_T1_AD2P_15_A13") (pintype "bidirectional"))
    )
    (net (code "74") (name "/DQ12") (class "Default")
      (node (ref "U4") (pin "A8") (pinfunction "IO_L2P_T0_AD8P_15_A8") (pintype "bidirectional"))
    )
    (net (code "75") (name "/DQ13") (class "Default")
      (node (ref "U4") (pin "A12") (pinfunction "IO_L5N_T0_AD9N_15_A12") (pintype "bidirectional"))
    )
    (net (code "76") (name "/DQ14") (class "Default")
      (node (ref "U4") (pin "A9") (pinfunction "IO_L2N_T0_AD8N_15_A9") (pintype "bidirectional"))
    )
    (net (code "77") (name "/DQ15") (class "Default")
      (node (ref "U4") (pin "B10") (pinfunction "IO_L4P_T0_15_B10") (pintype "bidirectional"))
    )
    (net (code "79") (name "/E1") (class "Default")
      (node (ref "U4") (pin "D1") (pinfunction "IO_L10N_T1_AD15N_35_D1") (pintype "bidirectional"))
    )
    (net (code "80") (name "/E2") (class "Default")
      (node (ref "U4") (pin "B2") (pinfunction "IO_L8P_T1_AD14P_35_B2") (pintype "bidirectional"))
    )
    (net (code "81") (name "/E3") (class "Default")
      (node (ref "U4") (pin "C3") (pinfunction "IO_L7P_T1_AD6P_35_C3") (pintype "bidirectional"))
    )
    (net (code "82") (name "/E5") (class "Default")
      (node (ref "U4") (pin "C2") (pinfunction "IO_L7N_T1_AD6N_35_C2") (pintype "bidirectional"))
    )
    (net (code "83") (name "/E6") (class "Default")
      (node (ref "U4") (pin "H5") (pinfunction "IO_L18P_T2_35_H5") (pintype "bidirectional"))
    )
    (net (code "84") (name "/F2") (class "Default")
      (node (ref "U4") (pin "C1") (pinfunction "IO_L9P_T1_DQS_AD7P_35_C1") (pintype "bidirectional"))
    )
    (net (code "85") (name "/F3") (class "Default")
      (node (ref "U4") (pin "F2") (pinfunction "IO_L15P_T2_DQS_35_F2") (pintype "bidirectional"))
    )
    (net (code "86") (name "/F4") (class "Default")
      (node (ref "U4") (pin "F3") (pinfunction "IO_L14N_T2_SRCC_35_F3") (pintype "bidirectional"))
    )
    (net (code "87") (name "/F5") (class "Default")
      (node (ref "U4") (pin "E3") (pinfunction "IO_L11P_T1_SRCC_35_E3") (pintype "bidirectional"))
    )
    (net (code "88") (name "/G1") (class "Default")
      (node (ref "U4") (pin "H3") (pinfunction "IO_L21N_T3_DQS_35_H3") (pintype "bidirectional"))
    )
    (net (code "89") (name "/G2") (class "Default")
      (node (ref "U4") (pin "H2") (pinfunction "IO_L20P_T3_35_H2") (pintype "bidirectional"))
    )
    (net (code "90") (name "/G4") (class "Default")
      (node (ref "U4") (pin "G1") (pinfunction "IO_L17N_T2_35_G1") (pintype "bidirectional"))
    )
    (net (code "91") (name "/G5") (class "Default")
      (node (ref "U4") (pin "H4") (pinfunction "IO_L18N_T2_35_H4") (pintype "bidirectional"))
    )
    (net (code "92") (name "/H1") (class "Default")
      (node (ref "U4") (pin "J4") (pinfunction "IO_L19N_T3_VREF_35_J4") (pintype "bidirectional"))
    )
    (net (code "93") (name "/H2") (class "Default")
      (node (ref "U4") (pin "J3") (pinfunction "IO_L21P_T3_DQS_35_J3") (pintype "bidirectional"))
    )
    (net (code "94") (name "/H3") (class "Default")
      (node (ref "U4") (pin "L2") (pinfunction "IO_L23N_T3_35_L2") (pintype "bidirectional"))
    )
    (net (code "95") (name "/H4") (class "Default")
      (node (ref "U4") (pin "L3") (pinfunction "IO_L23P_T3_35_L3") (pintype "bidirectional"))
    )
    (net (code "96") (name "/H5") (class "Default")
      (node (ref "U4") (pin "K3") (pinfunction "IO_L24P_T3_35_K3") (pintype "bidirectional"))
    )
    (net (code "97") (name "/IN_Filter_ADC_N") (class "Default")
      (node (ref "R21") (pin "2") (pinfunction "2_2") (pintype "passive"))
    )
    (net (code "98") (name "/IN_Filter_ADC_P") (class "Default")
      (node (ref "R20") (pin "2") (pinfunction "2_2") (pintype "passive"))
    )
    (net (code "99") (name "/J1") (class "Default")
      (node (ref "U4") (pin "J5") (pinfunction "IO_L19P_T3_35_J5") (pintype "bidirectional"))
    )
    (net (code "100") (name "/J3") (class "Default")
      (node (ref "U4") (pin "K2") (pinfunction "IO_L24N_T3_35_K2") (pintype "bidirectional"))
    )
    (net (code "101") (name "/J4") (class "Default")
      (node (ref "U4") (pin "J1") (pinfunction "IO_L22N_T3_35_J1") (pintype "bidirectional"))
    )
    (net (code "102") (name "/J5") (class "Default")
      (node (ref "U4") (pin "H1") (pinfunction "IO_L20N_T3_35_H1") (pintype "bidirectional"))
    )
    (net (code "103") (name "/K1") (class "Default")
      (node (ref "U4") (pin "K5") (pinfunction "IO_25_35_K5") (pintype "bidirectional"))
    )
    (net (code "104") (name "/K2") (class "Default")
      (node (ref "U4") (pin "G4") (pinfunction "IO_L16N_T2_35_G4") (pintype "bidirectional"))
    )
    (net (code "105") (name "/K3") (class "Default")
      (node (ref "U4") (pin "G5") (pinfunction "IO_L16P_T2_35_G5") (pintype "bidirectional"))
    )
    (net (code "106") (name "/K5") (class "Default")
      (node (ref "U4") (pin "E6") (pinfunction "IO_0_35_E6") (pintype "bidirectional"))
    )
    (net (code "107") (name "/K13") (class "Default")
      (node (ref "U4") (pin "N6") (pinfunction "IO_L19N_T3_A09_D25_VREF_14_N6") (pintype "bidirectional"))
    )
    (net (code "108") (name "/L1_N") (class "Default")
      (node (ref "U4") (pin "P1") (pinfunction "IO_L4N_T0_34_P1") (pintype "bidirectional"))
    )
    (net (code "109") (name "/L1_P") (class "Default")
      (node (ref "U4") (pin "N1") (pinfunction "IO_L4P_T0_34_N1") (pintype "bidirectional"))
    )
    (net (code "110") (name "/L2") (class "Default")
      (node (ref "U4") (pin "G2") (pinfunction "IO_L17P_T2_35_G2") (pintype "bidirectional"))
    )
    (net (code "111") (name "/L2_N") (class "Default")
      (node (ref "U4") (pin "M4") (pinfunction "IO_L1N_T0_34_M4") (pintype "bidirectional"))
    )
    (net (code "112") (name "/L2_P") (class "Default")
      (node (ref "U4") (pin "L4") (pinfunction "IO_L1P_T0_34_L4") (pintype "bidirectional"))
    )
    (net (code "113") (name "/L3") (class "Default")
      (node (ref "U4") (pin "K1") (pinfunction "IO_L22P_T3_35_K1") (pintype "bidirectional"))
    )
    (net (code "114") (name "/L3_N") (class "Default")
      (node (ref "U4") (pin "R1") (pinfunction "IO_L7N_T1_34_R1") (pintype "bidirectional"))
    )
    (net (code "115") (name "/L3_P") (class "Default")
      (node (ref "U4") (pin "R2") (pinfunction "IO_L7P_T1_34_R2") (pintype "bidirectional"))
    )
    (net (code "116") (name "/L4_N") (class "Default")
      (node (ref "U4") (pin "M1") (pinfunction "IO_L2N_T0_34_M1") (pintype "bidirectional"))
    )
    (net (code "117") (name "/L4_P") (class "Default")
      (node (ref "U4") (pin "M2") (pinfunction "IO_L2P_T0_34_M2") (pintype "bidirectional"))
    )
    (net (code "118") (name "/L5") (class "Default")
      (node (ref "U4") (pin "L5") (pinfunction "IO_0_34_L5") (pintype "bidirectional"))
    )
    (net (code "119") (name "/L5_N") (class "Default")
      (node (ref "U4") (pin "T2") (pinfunction "IO_L8N_T1_34_T2") (pintype "bidirectional"))
    )
    (net (code "120") (name "/L5_P") (class "Default")
      (node (ref "U4") (pin "R3") (pinfunction "IO_L8P_T1_34_R3") (pintype "bidirectional"))
    )
    (net (code "121") (name "/L6_N") (class "Default")
      (node (ref "U4") (pin "N2") (pinfunction "IO_L3N_T0_DQS_34_N2") (pintype "bidirectional"))
    )
    (net (code "122") (name "/L6_P") (class "Default")
      (node (ref "U4") (pin "N3") (pinfunction "IO_L3P_T0_DQS_34_N3") (pintype "bidirectional"))
    )
    (net (code "123") (name "/L7_N") (class "Default")
      (node (ref "U4") (pin "T3") (pinfunction "IO_L9N_T1_DQS_34_T3") (pintype "bidirectional"))
    )
    (net (code "124") (name "/L7_P") (class "Default")
      (node (ref "U4") (pin "T4") (pinfunction "IO_L9P_T1_DQS_34_T4") (pintype "bidirectional"))
    )
    (net (code "125") (name "/L8_N") (class "Default")
      (node (ref "U4") (pin "P3") (pinfunction "IO_L5N_T0_34_P3") (pintype "bidirectional"))
    )
    (net (code "126") (name "/L8_P") (class "Default")
      (node (ref "U4") (pin "P4") (pinfunction "IO_L5P_T0_34_P4") (pintype "bidirectional"))
    )
    (net (code "127") (name "/L9_N") (class "Default")
      (node (ref "U4") (pin "N4") (pinfunction "IO_L6N_T0_VREF_34_N4") (pintype "bidirectional"))
    )
    (net (code "128") (name "/L9_P") (class "Default")
      (node (ref "U4") (pin "M5") (pinfunction "IO_L6P_T0_34_M5") (pintype "bidirectional"))
    )
    (net (code "129") (name "/L13") (class "Default")
      (node (ref "U4") (pin "M14") (pinfunction "IO_L4N_T0_D05_14_M14") (pintype "bidirectional"))
    )
    (net (code "130") (name "/LDM") (class "Default")
      (node (ref "U4") (pin "B14") (pinfunction "IO_L8N_T1_AD10N_15_B14") (pintype "bidirectional"))
    )
    (net (code "131") (name "/LDQS_N") (class "Default")
      (node (ref "U4") (pin "E16") (pinfunction "IO_L17P_T2_A26_15_E16") (pintype "bidirectional"))
    )
    (net (code "132") (name "/LDQS_P") (class "Default")
      (node (ref "U4") (pin "D16") (pinfunction "IO_L17N_T2_A25_15_D16") (pintype "bidirectional"))
    )
    (net (code "133") (name "/LED0") (class "Default")
      (node (ref "U4") (pin "T15") (pinfunction "IO_L10N_T1_D15_14_T15") (pintype "bidirectional"))
    )
    (net (code "134") (name "/LED1") (class "Default")
      (node (ref "U4") (pin "R15") (pinfunction "IO_L9P_T1_DQS_14_R15") (pintype "bidirectional"))
    )
    (net (code "135") (name "/LED2") (class "Default")
      (node (ref "U4") (pin "R16") (pinfunction "IO_L9N_T1_DQS_D13_14_R16") (pintype "bidirectional"))
    )
    (net (code "136") (name "/LED3") (class "Default")
      (node (ref "U4") (pin "P15") (pinfunction "IO_L8P_T1_D11_14_P15") (pintype "bidirectional"))
    )
    (net (code "137") (name "/LED4") (class "Default")
      (node (ref "U4") (pin "P16") (pinfunction "IO_L8N_T1_D12_14_P16") (pintype "bidirectional"))
    )
    (net (code "138") (name "/LED5") (class "Default")
      (node (ref "U4") (pin "N16") (pinfunction "IO_L7N_T1_D10_14_N16") (pintype "bidirectional"))
    )
    (net (code "139") (name "/LED6") (class "Default")
      (node (ref "U4") (pin "M15") (pinfunction "IO_L3N_T0_DQS_EMCCLK_14_M15") (pintype "bidirectional"))
    )
    (net (code "140") (name "/LED7") (class "Default")
      (node (ref "U4") (pin "M16") (pinfunction "IO_L7P_T1_D09_14_M16") (pintype "bidirectional"))
    )
    (net (code "141") (name "/M6") (class "Default")
      (node (ref "U4") (pin "L14") (pinfunction "IO_L4P_T0_D04_14_L14") (pintype "bidirectional"))
    )
    (net (code "142") (name "/M15") (class "Default")
      (node (ref "U4") (pin "P8") (pinfunction "IO_L20P_T3_A08_D24_14_P8") (pintype "bidirectional"))
    )
    (net (code "143") (name "/N6") (class "Default")
      (node (ref "U4") (pin "M12") (pinfunction "IO_L6N_T0_D08_VREF_14_M12") (pintype "bidirectional"))
    )
    (net (code "144") (name "/N9") (class "Default")
      (node (ref "U4") (pin "T9") (pinfunction "IO_L22P_T3_A05_D21_14_T9") (pintype "bidirectional"))
    )
    (net (code "145") (name "/N11") (class "Default")
      (node (ref "U4") (pin "P11") (pinfunction "IO_L14N_T2_SRCC_14_P11") (pintype "bidirectional"))
    )
    (net (code "146") (name "/N12") (class "Default")
      (node (ref "U4") (pin "N12") (pinfunction "IO_L13N_T2_MRCC_14_N12") (pintype "bidirectional"))
    )
    (net (code "147") (name "/N13") (class "Default")
      (node (ref "U4") (pin "P9") (pinfunction "IO_L18N_T2_A11_D27_14_P9") (pintype "bidirectional"))
    )
    (net (code "148") (name "/ODT") (class "Default")
      (node (ref "U4") (pin "G15") (pinfunction "IO_L24N_T3_RS0_15_G15") (pintype "bidirectional"))
    )
    (net (code "149") (name "/P5") (class "Default")
      (node (ref "U4") (pin "P5") (pinfunction "IO_L10P_T1_34_P5") (pintype "bidirectional"))
    )
    (net (code "150") (name "/P8") (class "Default")
      (node (ref "U4") (pin "T8") (pinfunction "IO_L21N_T3_DQS_A06_D22_14_T8") (pintype "bidirectional"))
    )
    (net (code "151") (name "/P9") (class "Default")
      (node (ref "U4") (pin "R8") (pinfunction "IO_L20N_T3_A07_D23_14_R8") (pintype "bidirectional"))
    )
    (net (code "152") (name "/P10") (class "Default")
      (node (ref "U4") (pin "R10") (pinfunction "IO_L17P_T2_A14_D30_14_R10") (pintype "bidirectional"))
    )
    (net (code "153") (name "/P11") (class "Default")
      (node (ref "U4") (pin "T12") (pinfunction "IO_L15N_T2_DQS_DOUT_CSO_B_14_T12") (pintype "bidirectional"))
    )
    (net (code "154") (name "/P13") (class "Default")
      (node (ref "U4") (pin "N9") (pinfunction "IO_L18P_T2_A12_D28_14_N9") (pintype "bidirectional"))
    )
    (net (code "155") (name "/P14") (class "Default")
      (node (ref "U4") (pin "T10") (pinfunction "IO_L22N_T3_A04_D20_14_T10") (pintype "bidirectional"))
    )
    (net (code "156") (name "/PROGRAM_B") (class "Default")
      (node (ref "R19") (pin "1") (pinfunction "1_1") (pintype "passive"))
      (node (ref "U4") (pin "L9") (pinfunction "PROGRAM_B_0_L9") (pintype "input"))
    )
    (net (code "157") (name "/QSPI_CLK") (class "Default")
      (node (ref "U4") (pin "E8") (pinfunction "CCLK_0_E8") (pintype "bidirectional"))
    )
    (net (code "158") (name "/QSPI_DATA0") (class "Default")
      (node (ref "U4") (pin "K16") (pinfunction "IO_L2N_T0_D03_14_K16") (pintype "bidirectional"))
    )
    (net (code "159") (name "/QSPI_DATA1") (class "Default")
      (node (ref "U4") (pin "J14") (pinfunction "IO_L1N_T0_D01_DIN_14_J14") (pintype "bidirectional"))
    )
    (net (code "160") (name "/QSPI_DATA2") (class "Default")
      (node (ref "U4") (pin "K15") (pinfunction "IO_L2P_T0_D02_14_K15") (pintype "bidirectional"))
    )
    (net (code "161") (name "/QSPI_DATA3") (class "Default")
      (node (ref "U4") (pin "J13") (pinfunction "IO_L1P_T0_D00_MOSI_14_J13") (pintype "bidirectional"))
    )
    (net (code "162") (name "/QSPI_~{CS}") (class "Default")
      (node (ref "U4") (pin "L12") (pinfunction "IO_L6P_T0_FCS_B_14_L12") (pintype "bidirectional"))
    )
    (net (code "163") (name "/R7") (class "Default")
      (node (ref "U4") (pin "T5") (pinfunction "IO_L23N_T3_A02_D18_14_T5") (pintype "bidirectional"))
    )
    (net (code "164") (name "/R8") (class "Default")
      (node (ref "U4") (pin "T7") (pinfunction "IO_L21P_T3_DQS_14_T7") (pintype "bidirectional"))
    )
    (net (code "165") (name "/R10") (class "Default")
      (node (ref "U4") (pin "N13") (pinfunction "IO_L11P_T1_SRCC_14_N13") (pintype "bidirectional"))
    )
    (net (code "166") (name "/R11") (class "Default")
      (node (ref "U4") (pin "N14") (pinfunction "IO_L12P_T1_MRCC_14_N14") (pintype "bidirectional"))
    )
    (net (code "167") (name "/R12") (class "Default")
      (node (ref "U4") (pin "P14") (pinfunction "IO_L12N_T1_MRCC_14_P14") (pintype "bidirectional"))
    )
    (net (code "168") (name "/R13") (class "Default")
      (node (ref "U4") (pin "R11") (pinfunction "IO_L17N_T2_A13_D29_14_R11") (pintype "bidirectional"))
    )
    (net (code "169") (name "/R15") (class "Default")
      (node (ref "U4") (pin "T13") (pinfunction "IO_L16N_T2_A15_D31_14_T13") (pintype "bidirectional"))
    )
    (net (code "170") (name "/R16") (class "Default")
      (node (ref "U4") (pin "R12") (pinfunction "IO_L15P_T2_DQS_RDWR_B_14_R12") (pintype "bidirectional"))
    )
    (net (code "171") (name "/RESET") (class "Default")
      (node (ref "U4") (pin "R5") (pinfunction "IO_L23P_T3_A03_D19_14_R5") (pintype "bidirectional"))
    )
    (net (code "172") (name "/T5") (class "Default")
      (node (ref "U4") (pin "K13") (pinfunction "IO_L5P_T0_D06_14_K13") (pintype "bidirectional"))
    )
    (net (code "173") (name "/T7") (class "Default")
      (node (ref "U4") (pin "K12") (pinfunction "IO_0_14_K12") (pintype "bidirectional"))
    )
    (net (code "174") (name "/T8") (class "Default")
      (node (ref "U4") (pin "L13") (pinfunction "IO_L5N_T0_D07_14_L13") (pintype "bidirectional"))
    )
    (net (code "175") (name "/T9") (class "Default")
      (node (ref "U4") (pin "R7") (pinfunction "IO_L24N_T3_A00_D16_14_R7") (pintype "bidirectional"))
    )
    (net (code "176") (name "/T10") (class "Default")
      (node (ref "U4") (pin "M6") (pinfunction "IO_L19P_T3_A10_D26_14_M6") (pintype "bidirectional"))
    )
    (net (code "177") (name "/T12") (class "Default")
      (node (ref "U4") (pin "P13") (pinfunction "IO_L11N_T1_SRCC_14_P13") (pintype "bidirectional"))
    )
    (net (code "178") (name "/T13") (class "Default")
      (node (ref "U4") (pin "P10") (pinfunction "IO_L14P_T2_SRCC_14_P10") (pintype "bidirectional"))
    )
    (net (code "179") (name "/T14") (class "Default")
      (node (ref "U4") (pin "T14") (pinfunction "IO_L10P_T1_D14_14_T14") (pintype "bidirectional"))
    )
    (net (code "180") (name "/T15") (class "Default")
      (node (ref "U4") (pin "R13") (pinfunction "IO_L16P_T2_CSI_B_14_R13") (pintype "bidirectional"))
    )
    (net (code "181") (name "/UART_RX") (class "Default")
      (node (ref "U4") (pin "P6") (pinfunction "IO_25_14_P6") (pintype "bidirectional"))
    )
    (net (code "182") (name "/UART_TX") (class "Default")
      (node (ref "U4") (pin "R6") (pinfunction "IO_L24P_T3_A01_D17_14_R6") (pintype "bidirectional"))
    )
    (net (code "183") (name "/UDM") (class "Default")
      (node (ref "U4") (pin "B15") (pinfunction "IO_L9P_T1_DQS_AD3P_15_B15") (pintype "bidirectional"))
    )
    (net (code "184") (name "/UDQS_N") (class "Default")
      (node (ref "U4") (pin "B16") (pinfunction "IO_L10N_T1_AD11N_15_B16") (pintype "bidirectional"))
    )
    (net (code "185") (name "/UDQS_P") (class "Default")
      (node (ref "U4") (pin "C16") (pinfunction "IO_L10P_T1_AD11P_15_C16") (pintype "bidirectional"))
    )
    (net (code "186") (name "/~{CAS}") (class "Default")
      (node (ref "U4") (pin "C11") (pinfunction "IO_L11P_T1_SRCC_15_C11") (pintype "bidirectional"))
    )
    (net (code "187") (name "/~{CS}") (class "Default")
      (node (ref "U4") (pin "J16") (pinfunction "IO_L23N_T3_FWE_B_15_J16") (pintype "bidirectional"))
    )
    (net (code "188") (name "/~{DDR_RESET}") (class "Default")
      (node (ref "U4") (pin "J15") (pinfunction "IO_L23P_T3_FOE_B_15_J15") (pintype "bidirectional"))
    )
    (net (code "189") (name "/~{RAS}") (class "Default")
      (node (ref "U4") (pin "C9") (pinfunction "IO_L1N_T0_AD0N_15_C9") (pintype "bidirectional"))
    )
    (net (code "190") (name "/~{WE}") (class "Default")
      (node (ref "U4") (pin "D10") (pinfunction "IO_0_15_D10") (pintype "bidirectional"))
    )
    (net (code "191") (name "AGND") (class "Default")
      (node (ref "C38") (pin "1") (pinfunction "1_1") (pintype "passive"))
      (node (ref "C51") (pin "1") (pinfunction "1_1") (pintype "passive"))
      (node (ref "C52") (pin "1") (pinfunction "1_1") (pintype "passive"))
      (node (ref "C53") (pin "1") (pinfunction "1_1") (pintype "passive"))
      (node (ref "L4") (pin "2") (pinfunction "2_2") (pintype "passive"))
      (node (ref "U4") (pin "G7") (pinfunction "GNDADC_0_G7") (pintype "power_in"))
      (node (ref "U4") (pin "H7") (pinfunction "VREFN_0_H7") (pintype "power_in"))
      (node (ref "U5") (pin "3") (pinfunction "GND_3") (pintype "passive"))
    )
    (net (code "192") (name "GND") (class "Default")
      (node (ref "C22") (pin "1") (pinfunction "1_1") (pintype "passive"))
      (node (ref "C23") (pin "1") (pinfunction "1_1") (pintype "passive"))
      (node (ref "C24") (pin "1") (pinfunction "1_1") (pintype "passive"))
      (node (ref "C25") (pin "1") (pinfunction "1_1") (pintype "passive"))
      (node (ref "C26") (pin "1") (pinfunction "1_1") (pintype "passive"))
      (node (ref "C27") (pin "1") (pinfunction "1_1") (pintype "passive"))
      (node (ref "C28") (pin "1") (pinfunction "1_1") (pintype "passive"))
      (node (ref "C29") (pin "1") (pinfunction "1_1") (pintype "passive"))
      (node (ref "C30") (pin "1") (pinfunction "1_1") (pintype "passive"))
      (node (ref "C31") (pin "1") (pinfunction "1_1") (pintype "passive"))
      (node (ref "C32") (pin "1") (pinfunction "1_1") (pintype "passive"))
      (node (ref "C33") (pin "1") (pinfunction "1_1") (pintype "passive"))
      (node (ref "C34") (pin "1") (pinfunction "1_1") (pintype "passive"))
      (node (ref "C35") (pin "1") (pinfunction "1_1") (pintype "passive"))
      (node (ref "C36") (pin "1") (pinfunction "1_1") (pintype "passive"))
      (node (ref "C37") (pin "1") (pinfunction "1_1") (pintype "passive"))
      (node (ref "C39") (pin "1") (pinfunction "1_1") (pintype "passive"))
      (node (ref "C40") (pin "1") (pinfunction "1_1") (pintype "passive"))
      (node (ref "C41") (pin "1") (pinfunction "1_1") (pintype "passive"))
      (node (ref "C42") (pin "1") (pinfunction "1_1") (pintype "passive"))
      (node (ref "C43") (pin "1") (pinfunction "1_1") (pintype "passive"))
      (node (ref "C44") (pin "1") (pinfunction "1_1") (pintype "passive"))
      (node (ref "C45") (pin "1") (pinfunction "1_1") (pintype "passive"))
      (node (ref "C46") (pin "1") (pinfunction "1_1") (pintype "passive"))
      (node (ref "C47") (pin "1") (pinfunction "1_1") (pintype "passive"))
      (node (ref "C48") (pin "1") (pinfunction "1_1") (pintype "passive"))
      (node (ref "C49") (pin "1") (pinfunction "1_1") (pintype "passive"))
      (node (ref "C50") (pin "1") (pinfunction "1_1") (pintype "passive"))
      (node (ref "C55") (pin "1") (pinfunction "1_1") (pintype "passive"))
      (node (ref "C56") (pin "1") (pinfunction "1_1") (pintype "passive"))
      (node (ref "C57") (pin "1") (pinfunction "1_1") (pintype "passive"))
      (node (ref "C58") (pin "1") (pinfunction "1_1") (pintype "passive"))
      (node (ref "C59") (pin "1") (pinfunction "1_1") (pintype "passive"))
      (node (ref "C60") (pin "1") (pinfunction "1_1") (pintype "passive"))
      (node (ref "C61") (pin "1") (pinfunction "1_1") (pintype "passive"))
      (node (ref "C62") (pin "1") (pinfunction "1_1") (pintype "passive"))
      (node (ref "C63") (pin "1") (pinfunction "1_1") (pintype "passive"))
      (node (ref "C64") (pin "1") (pinfunction "1_1") (pintype "passive"))
      (node (ref "C65") (pin "1") (pinfunction "1_1") (pintype "passive"))
      (node (ref "C66") (pin "1") (pinfunction "1_1") (pintype "passive"))
      (node (ref "C67") (pin "1") (pinfunction "1_1") (pintype "passive"))
      (node (ref "C68") (pin "1") (pinfunction "1_1") (pintype "passive"))
      (node (ref "D3") (pin "C") (pinfunction "C_C") (pintype "passive"))
      (node (ref "L4") (pin "1") (pinfunction "1_1") (pintype "passive"))
      (node (ref "U4") (pin "A1") (pinfunction "GND_A1") (pintype "power_in"))
      (node (ref "U4") (pin "A11") (pinfunction "GND_A11") (pintype "power_in"))
      (node (ref "U4") (pin "B8") (pinfunction "GND_B8") (pintype "power_in"))
      (node (ref "U4") (pin "C15") (pinfunction "GND_C15") (pintype "power_in"))
      (node (ref "U4") (pin "C5") (pinfunction "GND_C5") (pintype "power_in"))
      (node (ref "U4") (pin "D12") (pinfunction "GND_D12") (pintype "power_in"))
      (node (ref "U4") (pin "D2") (pinfunction "GND_D2") (pintype "power_in"))
      (node (ref "U4") (pin "E9") (pinfunction "GND_E9") (pintype "power_in"))
      (node (ref "U4") (pin "F10") (pinfunction "GND_F10") (pintype "power_in"))
      (node (ref "U4") (pin "F16") (pinfunction "GND_F16") (pintype "power_in"))
      (node (ref "U4") (pin "F6") (pinfunction "GND_F6") (pintype "power_in"))
      (node (ref "U4") (pin "F8") (pinfunction "VCCBATT_0_F8") (pintype "power_in"))
      (node (ref "U4") (pin "G13") (pinfunction "GND_G13") (pintype "power_in"))
      (node (ref "U4") (pin "G3") (pinfunction "GND_G3") (pintype "power_in"))
      (node (ref "U4") (pin "G9") (pinfunction "GND_G9") (pintype "power_in"))
      (node (ref "U4") (pin "H6") (pinfunction "GND_H6") (pintype "power_in"))
      (node (ref "U4") (pin "J11") (pinfunction "GND_J11") (pintype "power_in"))
      (node (ref "U4") (pin "J9") (pinfunction "GND_J9") (pintype "power_in"))
      (node (ref "U4") (pin "K14") (pinfunction "GND_K14") (pintype "power_in"))
      (node (ref "U4") (pin "K4") (pinfunction "GND_K4") (pintype "power_in"))
      (node (ref "U4") (pin "K6") (pinfunction "GND_K6") (pintype "power_in"))
      (node (ref "U4") (pin "K7") (pinfunction "DXN_0_K7") (pintype "input"))
      (node (ref "U4") (pin "K8") (pinfunction "DXP_0_K8") (pintype "input"))
      (node (ref "U4") (pin "L1") (pinfunction "GND_L1") (pintype "power_in"))
      (node (ref "U4") (pin "L11") (pinfunction "GND_L11") (pintype "power_in"))
      (node (ref "U4") (pin "M10") (pinfunction "M1_0_M10") (pintype "input"))
      (node (ref "U4") (pin "M11") (pinfunction "M2_0_M11") (pintype "input"))
      (node (ref "U4") (pin "M8") (pinfunction "GND_M8") (pintype "power_in"))
      (node (ref "U4") (pin "N15") (pinfunction "GND_N15") (pintype "power_in"))
      (node (ref "U4") (pin "N5") (pinfunction "GND_N5") (pintype "power_in"))
      (node (ref "U4") (pin "P12") (pinfunction "GND_P12") (pintype "power_in"))
      (node (ref "U4") (pin "P2") (pinfunction "GND_P2") (pintype "power_in"))
      (node (ref "U4") (pin "R9") (pinfunction "GND_R9") (pintype "power_in"))
      (node (ref "U4") (pin "T16") (pinfunction "GND_T16") (pintype "power_in"))
      (node (ref "U4") (pin "T6") (pinfunction "GND_T6") (pintype "power_in"))
      (node (ref "XTAL2") (pin "2") (pinfunction "GND_2") (pintype "power_in"))
    )
    (net (code "193") (name "Net-(D3-PadA)") (class "Default")
      (node (ref "D3") (pin "A") (pinfunction "A_A") (pintype "passive"))
      (node (ref "R17") (pin "2") (pinfunction "2_2") (pintype "passive"))
    )
    (net (code "194") (name "Net-(U4G-INIT_B_0)") (class "Default")
      (node (ref "R18") (pin "1") (pinfunction "1_1") (pintype "passive"))
      (node (ref "U4") (pin "K10") (pinfunction "INIT_B_0_K10") (pintype "bidirectional"))
    )
    (net (code "195") (name "unconnected-(U4C-IO_L19P_T3_A22_15-PadH11)") (class "Default")
      (node (ref "U4") (pin "H11") (pinfunction "IO_L19P_T3_A22_15_H11") (pintype "bidirectional+no_connect"))
    )
  )
)
